# Hfield1A.net
KiCad netlist of a schematic drawn in EAGLE
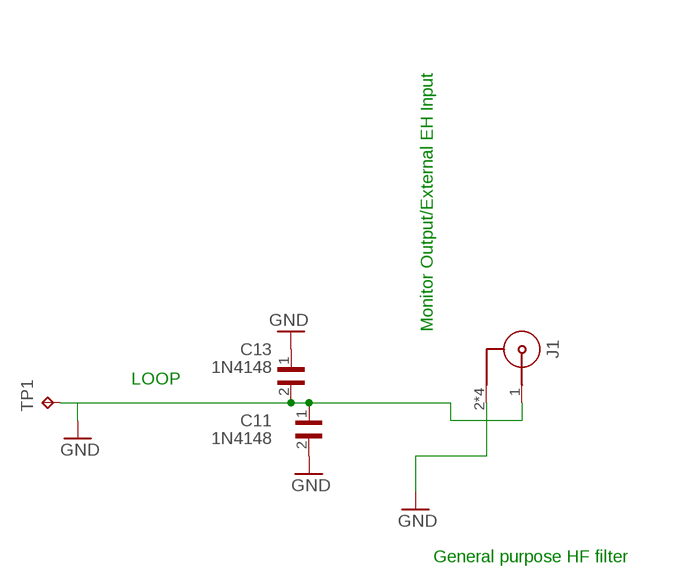
[diagram p0: schematic, sheet 1]

(export (version "E")
  (design (tool "Eeschema 10.0.6"))
  (components
    (comp (ref "C11")
      (value "1N4148")
      (footprint "eagle-import:WCAP-CSGP_0805_REFLOW")
      (libsource (lib "eagle-import") (part "WCAP-CSGP_0805-REFLOW"))
    )
    (comp (ref "C13")
      (value "1N4148")
      (footprint "eagle-import:WCAP-CSGP_0805_REFLOW")
      (libsource (lib "eagle-import") (part "WCAP-CSGP_0805-REFLOW"))
    )
    (comp (ref "J1")
      (value "60312202114509")
      (footprint "eagle-import:60312202114509")
      (libsource (lib "eagle-import") (part "60312202114509"))
    )
    (comp (ref "TP1")
      (value "TPB2,54")
      (footprint "eagle-import:B2,54")
      (libsource (lib "eagle-import") (part "TPB2,54"))
    )
  )
  (nets
    (net (code "1") (name "GND") (class "Default")
      (node (ref "C11") (pin "1") (pinfunction "1_1") (pintype "passive"))
      (node (ref "C11") (pin "2") (pinfunction "2_2") (pintype "passive"))
      (node (ref "C13") (pin "1") (pinfunction "1_1") (pintype "passive"))
      (node (ref "C13") (pin "2") (pinfunction "2_2") (pintype "passive"))
      (node (ref "J1") (pin "1") (pinfunction "1_1") (pintype "passive"))
      (node (ref "J1") (pin "2") (pinfunction "2_2") (pintype "passive"))
      (node (ref "J1") (pin "3") (pinfunction "2_3") (pintype "passive"))
      (node (ref "J1") (pin "4") (pinfunction "2_4") (pintype "passive"))
      (node (ref "J1") (pin "5") (pinfunction "2_5") (pintype "passive"))
      (node (ref "TP1") (pin "TP") (pinfunction "TP_TP") (pintype "input"))
    )
  )
)
